# br215.net
KiCad netlist of a schematic drawn in EAGLE
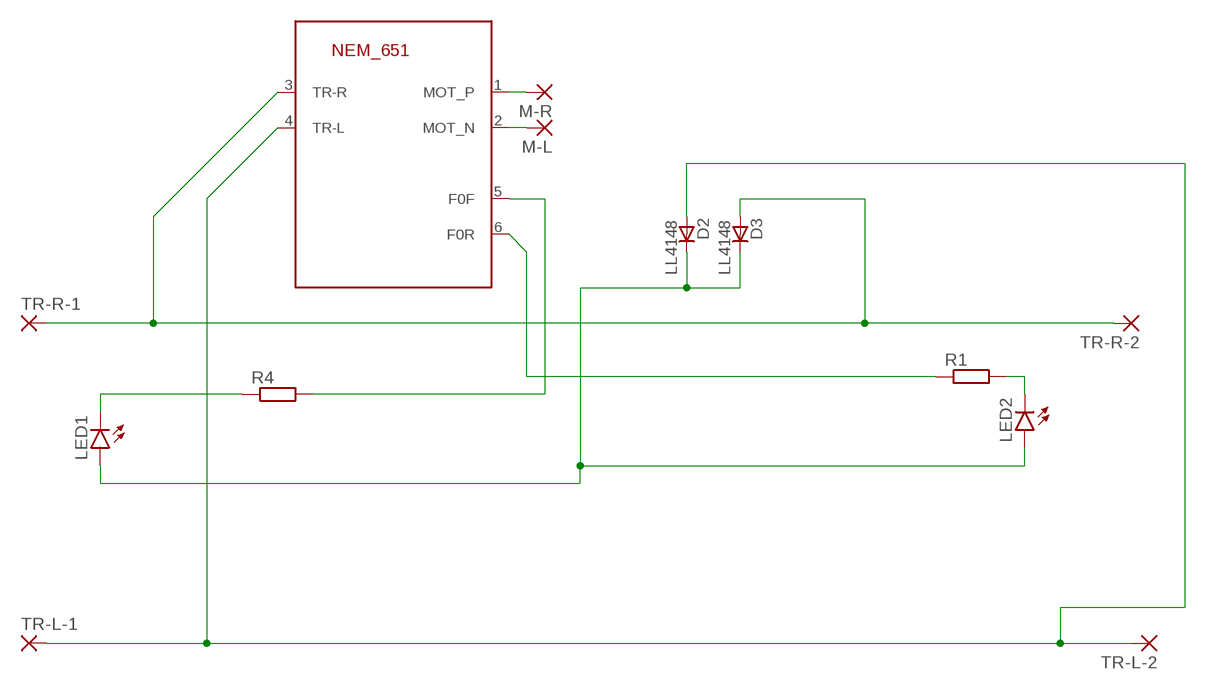
[diagram p0: schematic, sheet 1]

(export (version "E")
  (design (tool "Eeschema 10.0.6"))
  (components
    (comp (ref "651")
      (value "NEM_651-TS")
      (footprint "eagle-import:53047-06")
      (libsource (lib "eagle-import") (part "NEM_651-TS"))
    )
    (comp (ref "D2")
      (value "LL4148")
      (footprint "eagle-import:SOD80_DO213AA_MINIMELF")
      (libsource (lib "eagle-import") (part "LL4148"))
    )
    (comp (ref "D3")
      (value "LL4148")
      (footprint "eagle-import:SOD80_DO213AA_MINIMELF")
      (libsource (lib "eagle-import") (part "LL4148"))
    )
    (comp (ref "LED1")
      (value "LED3MM")
      (footprint "eagle-import:LED3MM")
      (libsource (lib "eagle-import") (part "LED3MM"))
    )
    (comp (ref "LED2")
      (value "LED3MM")
      (footprint "eagle-import:LED3MM")
      (libsource (lib "eagle-import") (part "LED3MM"))
    )
    (comp (ref "M-L")
      (value "SMD5")
      (footprint "eagle-import:SMD2,54-5,08")
      (libsource (lib "eagle-import") (part "SMD5"))
    )
    (comp (ref "M-R")
      (value "SMD5")
      (footprint "eagle-import:SMD2,54-5,08")
      (libsource (lib "eagle-import") (part "SMD5"))
    )
    (comp (ref "R1")
      (value "R-EU_R0603")
      (footprint "eagle-import:R0603")
      (libsource (lib "eagle-import") (part "R-EU_R0603"))
    )
    (comp (ref "R4")
      (value "R-EU_R0603")
      (footprint "eagle-import:R0603")
      (libsource (lib "eagle-import") (part "R-EU_R0603"))
    )
    (comp (ref "TR-L-1")
      (value "SMD5")
      (footprint "eagle-import:SMD2,54-5,08")
      (libsource (lib "eagle-import") (part "SMD5"))
    )
    (comp (ref "TR-L-2")
      (value "SMD5")
      (footprint "eagle-import:SMD2,54-5,08")
      (libsource (lib "eagle-import") (part "SMD5"))
    )
    (comp (ref "TR-R-1")
      (value "SMD5")
      (footprint "eagle-import:SMD2,54-5,08")
      (libsource (lib "eagle-import") (part "SMD5"))
    )
    (comp (ref "TR-R-2")
      (value "SMD5")
      (footprint "eagle-import:SMD2,54-5,08")
      (libsource (lib "eagle-import") (part "SMD5"))
    )
  )
  (nets
    (net (code "1") (name "Net-(651-F0F)") (class "Default")
      (node (ref "651") (pin "5") (pinfunction "F0F_5") (pintype "bidirectional"))
      (node (ref "R4") (pin "2") (pinfunction "2_2") (pintype "passive"))
    )
    (net (code "2") (name "Net-(651-F0R)") (class "Default")
      (node (ref "651") (pin "6") (pinfunction "F0R_6") (pintype "bidirectional"))
      (node (ref "R1") (pin "1") (pinfunction "1_1") (pintype "passive"))
    )
    (net (code "3") (name "Net-(651-MOT_N)") (class "Default")
      (node (ref "651") (pin "2") (pinfunction "MOT_N_2") (pintype "bidirectional"))
      (node (ref "M-L") (pin "1") (pinfunction "P_1") (pintype "passive"))
    )
    (net (code "4") (name "Net-(651-MOT_P)") (class "Default")
      (node (ref "651") (pin "1") (pinfunction "MOT_P_1") (pintype "bidirectional"))
      (node (ref "M-R") (pin "1") (pinfunction "P_1") (pintype "passive"))
    )
    (net (code "5") (name "Net-(651-TR-L)") (class "Default")
      (node (ref "651") (pin "4") (pinfunction "TR-L_4") (pintype "bidirectional"))
      (node (ref "D2") (pin "A") (pinfunction "A_A") (pintype "passive"))
      (node (ref "TR-L-1") (pin "1") (pinfunction "P_1") (pintype "passive"))
      (node (ref "TR-L-2") (pin "1") (pinfunction "P_1") (pintype "passive"))
    )
    (net (code "6") (name "Net-(651-TR-R)") (class "Default")
      (node (ref "651") (pin "3") (pinfunction "TR-R_3") (pintype "bidirectional"))
      (node (ref "D3") (pin "A") (pinfunction "A_A") (pintype "passive"))
      (node (ref "TR-R-1") (pin "1") (pinfunction "P_1") (pintype "passive"))
      (node (ref "TR-R-2") (pin "1") (pinfunction "P_1") (pintype "passive"))
    )
    (net (code "7") (name "Net-(D2-PadC)") (class "Default")
      (node (ref "D2") (pin "C") (pinfunction "C_C") (pintype "passive"))
      (node (ref "D3") (pin "C") (pinfunction "C_C") (pintype "passive"))
      (node (ref "LED1") (pin "A") (pinfunction "A_A") (pintype "passive"))
      (node (ref "LED2") (pin "A") (pinfunction "A_A") (pintype "passive"))
    )
    (net (code "8") (name "Net-(LED1-C)") (class "Default")
      (node (ref "LED1") (pin "K") (pinfunction "C_K") (pintype "passive"))
      (node (ref "R4") (pin "1") (pinfunction "1_1") (pintype "passive"))
    )
    (net (code "9") (name "Net-(LED2-C)") (class "Default")
      (node (ref "LED2") (pin "K") (pinfunction "C_K") (pintype "passive"))
      (node (ref "R1") (pin "2") (pinfunction "2_2") (pintype "passive"))
    )
  )
)
